# esp_4g_gp10-a.net
KiCad netlist of a schematic drawn in EasyEDA Pro
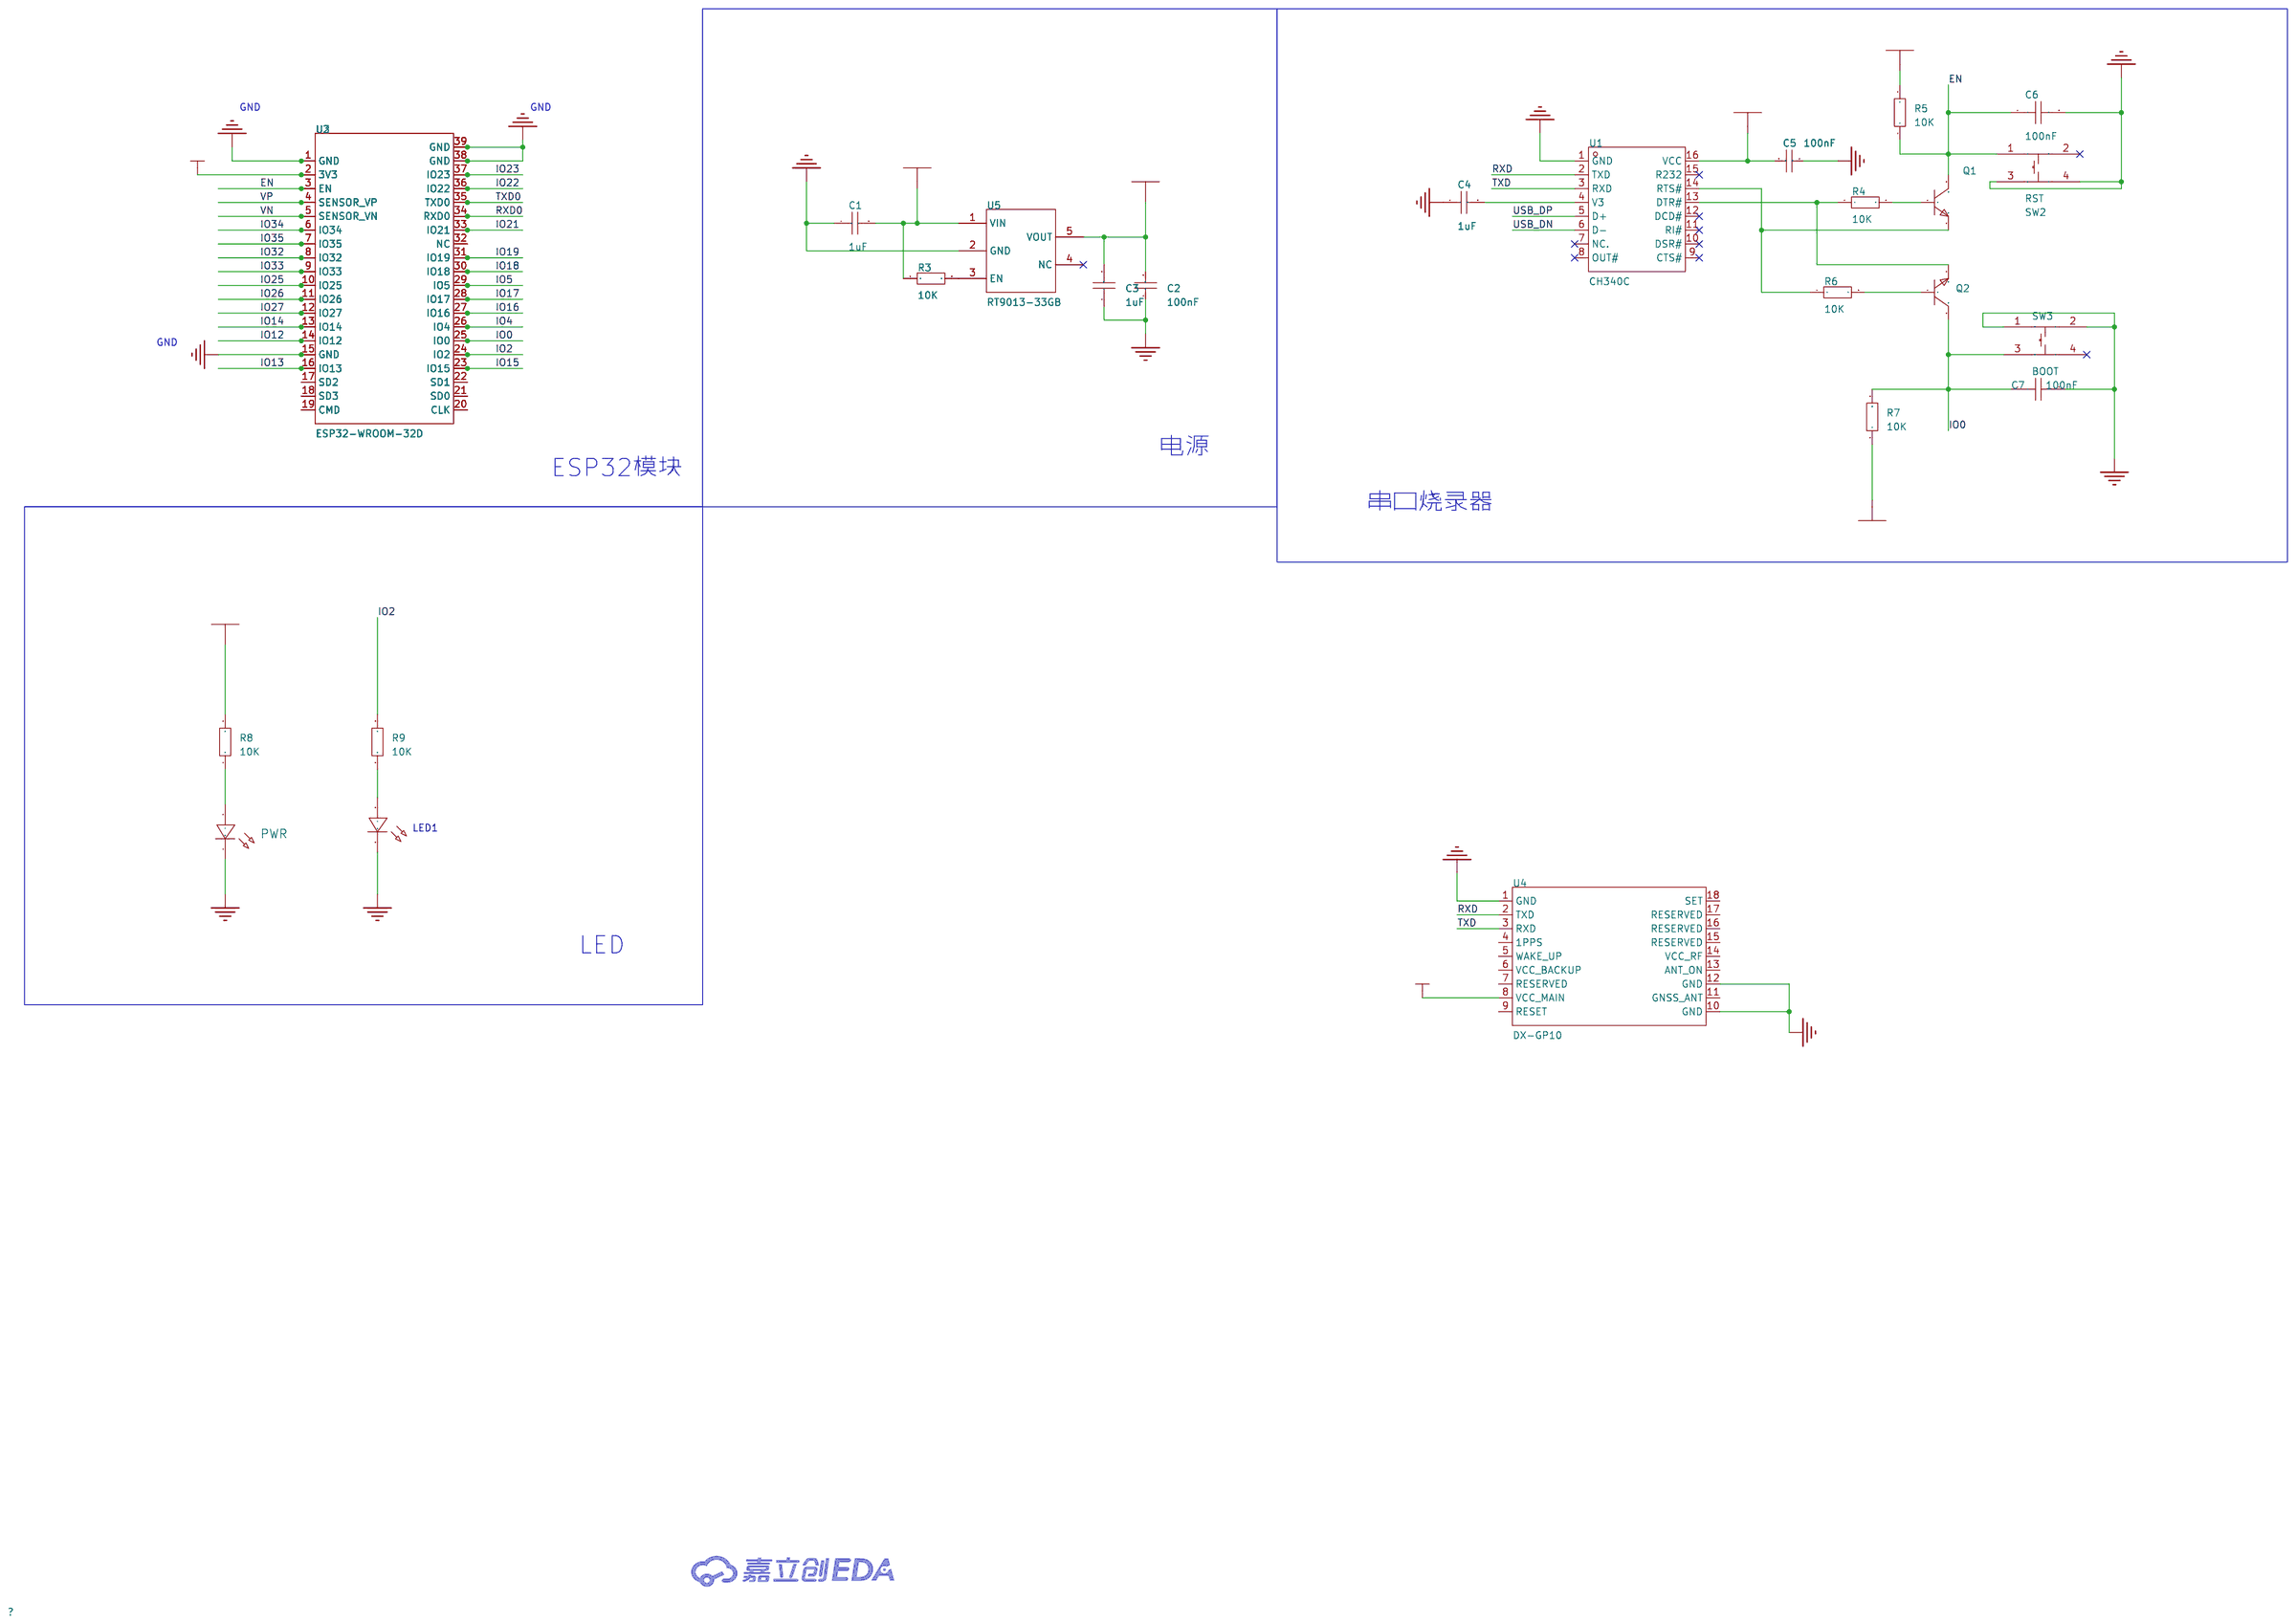
[diagram p0: schematic sheet]

(export (version "E")
  (design (tool "Eeschema 10.0.6"))
  (components
    (comp (ref "C1")
      (value "1uF")
      (footprint "easyedapro:C0603")
      (description "容值:1uF;精度:±20%;额定电压:25V;材质(温度系数):Y5V;")
      (fields (field (name "Manufacturer Part") "0603F105M250NT") (field (name "Manufacturer") "FH(风华)"))
      (libsource (lib "easyedapro") (part "0603F105M250NT"))
    )
    (comp (ref "C2")
      (value "100nF")
      (footprint "easyedapro:C0402")
      (description "温度系数:X7R;容值:100nF;精度:±5%;额定电压:16V;")
      (fields (field (name "Manufacturer Part") "0402B104J160NT") (field (name "Manufacturer") "FH(风华)"))
      (libsource (lib "easyedapro") (part "0402B104J160NT"))
    )
    (comp (ref "C3")
      (value "1uF")
      (footprint "easyedapro:C0603")
      (description "容值:1uF;精度:±20%;额定电压:25V;材质(温度系数):Y5V;")
      (fields (field (name "Manufacturer Part") "0603F105M250NT") (field (name "Manufacturer") "FH(风华)"))
      (libsource (lib "easyedapro") (part "0603F105M250NT"))
    )
    (comp (ref "C4")
      (value "1uF")
      (footprint "easyedapro:C0603")
      (description "容值:1uF;精度:±20%;额定电压:25V;材质(温度系数):Y5V;")
      (fields (field (name "Manufacturer Part") "0603F105M250NT") (field (name "Manufacturer") "FH(风华)"))
      (libsource (lib "easyedapro") (part "0603F105M250NT"))
    )
    (comp (ref "C5")
      (value "100nF")
      (footprint "easyedapro:C0402")
      (description "温度系数:X7R;容值:100nF;精度:±5%;额定电压:16V;")
      (fields (field (name "Manufacturer Part") "0402B104J160NT") (field (name "Manufacturer") "FH(风华)"))
      (libsource (lib "easyedapro") (part "0402B104J160NT"))
    )
    (comp (ref "C6")
      (value "100nF")
      (footprint "easyedapro:C0603")
      (libsource (lib "easyedapro") (part "CapAcitance"))
    )
    (comp (ref "C7")
      (value "100nF")
      (footprint "easyedapro:C0603")
      (libsource (lib "easyedapro") (part "CapAcitance"))
    )
    (comp (ref "LED1")
      (value "~")
      (footprint "easyedapro:LED_0603")
      (libsource (lib "easyedapro") (part "LED_G"))
    )
    (comp (ref "PWR")
      (value "~")
      (footprint "easyedapro:LED_0603")
      (libsource (lib "easyedapro") (part "LED_R"))
    )
    (comp (ref "Q1")
      (value "~")
      (footprint "easyedapro:S8050_SOT-23")
      (libsource (lib "easyedapro") (part "NPN"))
    )
    (comp (ref "Q2")
      (value "~")
      (footprint "easyedapro:S8050_SOT-23")
      (libsource (lib "easyedapro") (part "NPN"))
    )
    (comp (ref "R3") (value "10K") (footprint "easyedapro:R0603") (libsource (lib "easyedapro") (part "电阻")))
    (comp (ref "R4") (value "10K") (footprint "easyedapro:R0603") (libsource (lib "easyedapro") (part "电阻")))
    (comp (ref "R5") (value "10K") (footprint "easyedapro:R0603") (libsource (lib "easyedapro") (part "电阻")))
    (comp (ref "R6") (value "10K") (footprint "easyedapro:R0603") (libsource (lib "easyedapro") (part "电阻")))
    (comp (ref "R7") (value "10K") (footprint "easyedapro:R0603") (libsource (lib "easyedapro") (part "电阻")))
    (comp (ref "R8") (value "10K") (footprint "easyedapro:R0603") (libsource (lib "easyedapro") (part "电阻")))
    (comp (ref "R9") (value "10K") (footprint "easyedapro:R0603") (libsource (lib "easyedapro") (part "电阻")))
    (comp (ref "SW2")
      (value "RST")
      (footprint "easyedapro:KEY-SMD_4P-L4.2-W3.2-P2.20-LS4.6")
      (description "触点电流:50mA;额定电压(DC):16V;电路结构:单刀单掷;安装方式:立贴;按钮形状:椭圆形按钮;带灯:-;开关长度:4.2mm;开关宽度:3.2mm;开关高度:2.5mm;")
      (fields (field (name "Manufacturer") "ALPSALPINE(阿尔卑斯阿尔派)"))
      (libsource (lib "easyedapro") (part "SKRPACE010"))
    )
    (comp (ref "SW3")
      (value "BOOT")
      (footprint "easyedapro:KEY-SMD_4P-L4.2-W3.2-P2.20-LS4.6")
      (description "触点电流:50mA;额定电压(DC):16V;电路结构:单刀单掷;安装方式:立贴;按钮形状:椭圆形按钮;带灯:-;开关长度:4.2mm;开关宽度:3.2mm;开关高度:2.5mm;")
      (fields (field (name "Manufacturer") "ALPSALPINE(阿尔卑斯阿尔派)"))
      (libsource (lib "easyedapro") (part "SKRPACE010"))
    )
    (comp (ref "U1")
      (value "CH340C")
      (footprint "easyedapro:SOP-16_L10.0-W3.9-P1.27-LS6.0-BL")
      (description "应用功能:收发器;接口协议:USB 2.0;数据速率:2Mbps;")
      (fields (field (name "Manufacturer") "WCH(南京沁恒)"))
      (libsource (lib "easyedapro") (part "CH340C"))
    )
    (comp (ref "U2")
      (value "ESP32-WROOM-32D")
      (footprint "easyedapro:WIFIM-SMD_ESP32-WROOM-32D")
      (libsource (lib "easyedapro") (part "ESP32-WROOM-32D_C503588"))
    )
    (comp (ref "U3")
      (value "ESP32-WROOM-32D")
      (footprint "easyedapro:WIFIM-SMD_ESP32-WROOM-32D")
      (libsource (lib "easyedapro") (part "ESP32-WROOM-32D_C503588"))
    )
    (comp (ref "U4")
      (value "DX-GP10")
      (footprint "easyedapro:COMM-SMD_18P-L10.1-W9.7-P1.1-TL_L76-LB")
      (libsource (lib "easyedapro") (part "DX-GP10"))
    )
    (comp (ref "U5")
      (value "RT9013-33GB")
      (footprint "easyedapro:SOT-23-5_L3.0-W1.7-P0.95-LS2.8-BL")
      (description "输出类型:固定;最大输入电压:5.5V;输出电压:3.3V;输出电流:500mA;电源纹波抑制比(PSRR):50dB@(10kHz);输出极性:正极;")
      (fields (field (name "Manufacturer") "RICHTEK(立锜)"))
      (libsource (lib "easyedapro") (part "RT9013-33GB"))
    )
  )
  (nets
    (net (code "1") (name "/EN") (class "Default")
      (node (ref "C6") (pin "1") (pinfunction "1_1") (pintype "input"))
      (node (ref "Q1") (pin "3") (pinfunction "3_3") (pintype "unspecified"))
      (node (ref "R5") (pin "1") (pinfunction "1_1") (pintype "input"))
      (node (ref "SW2") (pin "1") (pinfunction "1_1") (pintype "input"))
      (node (ref "U2") (pin "3") (pinfunction "EN_3") (pintype "unspecified"))
      (node (ref "U3") (pin "3") (pinfunction "EN_3") (pintype "unspecified"))
    )
    (net (code "2") (name "/IO0") (class "Default")
      (node (ref "C7") (pin "1") (pinfunction "1_1") (pintype "input"))
      (node (ref "Q2") (pin "3") (pinfunction "3_3") (pintype "unspecified"))
      (node (ref "R7") (pin "2") (pinfunction "2_2") (pintype "input"))
      (node (ref "SW3") (pin "3") (pinfunction "3_3") (pintype "input"))
      (node (ref "U2") (pin "25") (pinfunction "IO0_25") (pintype "unspecified"))
      (node (ref "U3") (pin "25") (pinfunction "IO0_25") (pintype "unspecified"))
    )
    (net (code "3") (name "/IO2") (class "Default")
      (node (ref "R9") (pin "2") (pinfunction "2_2") (pintype "input"))
      (node (ref "U2") (pin "24") (pinfunction "IO2_24") (pintype "unspecified"))
      (node (ref "U3") (pin "24") (pinfunction "IO2_24") (pintype "unspecified"))
    )
    (net (code "4") (name "/IO4") (class "Default")
      (node (ref "U2") (pin "26") (pinfunction "IO4_26") (pintype "unspecified"))
      (node (ref "U3") (pin "26") (pinfunction "IO4_26") (pintype "unspecified"))
    )
    (net (code "5") (name "/IO5") (class "Default")
      (node (ref "U2") (pin "29") (pinfunction "IO5_29") (pintype "unspecified"))
      (node (ref "U3") (pin "29") (pinfunction "IO5_29") (pintype "unspecified"))
    )
    (net (code "6") (name "/IO12") (class "Default")
      (node (ref "U2") (pin "14") (pinfunction "IO12_14") (pintype "unspecified"))
      (node (ref "U3") (pin "14") (pinfunction "IO12_14") (pintype "unspecified"))
    )
    (net (code "7") (name "/IO13") (class "Default")
      (node (ref "U2") (pin "16") (pinfunction "IO13_16") (pintype "unspecified"))
      (node (ref "U3") (pin "16") (pinfunction "IO13_16") (pintype "unspecified"))
    )
    (net (code "8") (name "/IO14") (class "Default")
      (node (ref "U2") (pin "13") (pinfunction "IO14_13") (pintype "unspecified"))
      (node (ref "U3") (pin "13") (pinfunction "IO14_13") (pintype "unspecified"))
    )
    (net (code "9") (name "/IO15") (class "Default")
      (node (ref "U2") (pin "23") (pinfunction "IO15_23") (pintype "unspecified"))
      (node (ref "U3") (pin "23") (pinfunction "IO15_23") (pintype "unspecified"))
    )
    (net (code "10") (name "/IO16") (class "Default")
      (node (ref "U2") (pin "27") (pinfunction "IO16_27") (pintype "unspecified"))
      (node (ref "U3") (pin "27") (pinfunction "IO16_27") (pintype "unspecified"))
    )
    (net (code "11") (name "/IO17") (class "Default")
      (node (ref "U2") (pin "28") (pinfunction "IO17_28") (pintype "unspecified"))
      (node (ref "U3") (pin "28") (pinfunction "IO17_28") (pintype "unspecified"))
    )
    (net (code "12") (name "/IO18") (class "Default")
      (node (ref "U2") (pin "30") (pinfunction "IO18_30") (pintype "unspecified"))
      (node (ref "U3") (pin "30") (pinfunction "IO18_30") (pintype "unspecified"))
    )
    (net (code "13") (name "/IO19") (class "Default")
      (node (ref "U2") (pin "31") (pinfunction "IO19_31") (pintype "unspecified"))
      (node (ref "U3") (pin "31") (pinfunction "IO19_31") (pintype "unspecified"))
    )
    (net (code "14") (name "/IO21") (class "Default")
      (node (ref "U2") (pin "33") (pinfunction "IO21_33") (pintype "unspecified"))
      (node (ref "U3") (pin "33") (pinfunction "IO21_33") (pintype "unspecified"))
    )
    (net (code "15") (name "/IO22") (class "Default")
      (node (ref "U2") (pin "36") (pinfunction "IO22_36") (pintype "unspecified"))
      (node (ref "U3") (pin "36") (pinfunction "IO22_36") (pintype "unspecified"))
    )
    (net (code "16") (name "/IO23") (class "Default")
      (node (ref "U2") (pin "37") (pinfunction "IO23_37") (pintype "unspecified"))
      (node (ref "U3") (pin "37") (pinfunction "IO23_37") (pintype "unspecified"))
    )
    (net (code "17") (name "/IO25") (class "Default")
      (node (ref "U2") (pin "10") (pinfunction "IO25_10") (pintype "unspecified"))
      (node (ref "U3") (pin "10") (pinfunction "IO25_10") (pintype "unspecified"))
    )
    (net (code "18") (name "/IO26") (class "Default")
      (node (ref "U2") (pin "11") (pinfunction "IO26_11") (pintype "unspecified"))
      (node (ref "U3") (pin "11") (pinfunction "IO26_11") (pintype "unspecified"))
    )
    (net (code "19") (name "/IO27") (class "Default")
      (node (ref "U2") (pin "12") (pinfunction "IO27_12") (pintype "unspecified"))
      (node (ref "U3") (pin "12") (pinfunction "IO27_12") (pintype "unspecified"))
    )
    (net (code "20") (name "/IO32") (class "Default")
      (node (ref "U2") (pin "8") (pinfunction "IO32_8") (pintype "unspecified"))
      (node (ref "U3") (pin "8") (pinfunction "IO32_8") (pintype "unspecified"))
    )
    (net (code "21") (name "/IO33") (class "Default")
      (node (ref "U2") (pin "9") (pinfunction "IO33_9") (pintype "unspecified"))
      (node (ref "U3") (pin "9") (pinfunction "IO33_9") (pintype "unspecified"))
    )
    (net (code "22") (name "/IO34") (class "Default")
      (node (ref "U2") (pin "6") (pinfunction "IO34_6") (pintype "unspecified"))
      (node (ref "U3") (pin "6") (pinfunction "IO34_6") (pintype "unspecified"))
    )
    (net (code "23") (name "/IO35") (class "Default")
      (node (ref "U2") (pin "7") (pinfunction "IO35_7") (pintype "unspecified"))
      (node (ref "U3") (pin "7") (pinfunction "IO35_7") (pintype "unspecified"))
    )
    (net (code "24") (name "/RXD") (class "Default")
      (node (ref "U1") (pin "2") (pinfunction "TXD_2") (pintype "unspecified"))
      (node (ref "U4") (pin "2") (pinfunction "TXD_2") (pintype "unspecified"))
    )
    (net (code "25") (name "/RXD0") (class "Default")
      (node (ref "U2") (pin "34") (pinfunction "RXD0_34") (pintype "unspecified"))
      (node (ref "U3") (pin "34") (pinfunction "RXD0_34") (pintype "unspecified"))
    )
    (net (code "26") (name "/TXD") (class "Default")
      (node (ref "U1") (pin "3") (pinfunction "RXD_3") (pintype "unspecified"))
      (node (ref "U4") (pin "3") (pinfunction "RXD_3") (pintype "unspecified"))
    )
    (net (code "27") (name "/TXD0") (class "Default")
      (node (ref "U2") (pin "35") (pinfunction "TXD0_35") (pintype "unspecified"))
      (node (ref "U3") (pin "35") (pinfunction "TXD0_35") (pintype "unspecified"))
    )
    (net (code "28") (name "/USB_DN") (class "Default")
      (node (ref "U1") (pin "6") (pinfunction "D-_6") (pintype "unspecified"))
    )
    (net (code "29") (name "/USB_DP") (class "Default")
      (node (ref "U1") (pin "5") (pinfunction "D+_5") (pintype "unspecified"))
    )
    (net (code "30") (name "/VN") (class "Default")
      (node (ref "U2") (pin "5") (pinfunction "SENSOR_VN_5") (pintype "unspecified"))
      (node (ref "U3") (pin "5") (pinfunction "SENSOR_VN_5") (pintype "unspecified"))
    )
    (net (code "31") (name "/VP") (class "Default")
      (node (ref "U2") (pin "4") (pinfunction "SENSOR_VP_4") (pintype "unspecified"))
      (node (ref "U3") (pin "4") (pinfunction "SENSOR_VP_4") (pintype "unspecified"))
    )
    (net (code "32") (name "3.3V") (class "Default")
      (node (ref "U2") (pin "2") (pinfunction "3V3_2") (pintype "unspecified"))
      (node (ref "U3") (pin "2") (pinfunction "3V3_2") (pintype "unspecified"))
    )
    (net (code "33") (name "3V3") (class "Default")
      (node (ref "C2") (pin "2") (pinfunction "2_2") (pintype "input"))
      (node (ref "C3") (pin "2") (pinfunction "2_2") (pintype "input"))
      (node (ref "R5") (pin "2") (pinfunction "2_2") (pintype "input"))
      (node (ref "R7") (pin "1") (pinfunction "1_1") (pintype "input"))
      (node (ref "R8") (pin "2") (pinfunction "2_2") (pintype "input"))
      (node (ref "U5") (pin "5") (pinfunction "VOUT_5") (pintype "unspecified"))
    )
    (net (code "34") (name "GND") (class "Default")
      (node (ref "C1") (pin "1") (pinfunction "1_1") (pintype "input"))
      (node (ref "C2") (pin "1") (pinfunction "1_1") (pintype "input"))
      (node (ref "C3") (pin "1") (pinfunction "1_1") (pintype "input"))
      (node (ref "C4") (pin "1") (pinfunction "1_1") (pintype "input"))
      (node (ref "C5") (pin "1") (pinfunction "1_1") (pintype "input"))
      (node (ref "C6") (pin "2") (pinfunction "2_2") (pintype "input"))
      (node (ref "C7") (pin "2") (pinfunction "2_2") (pintype "input"))
      (node (ref "LED1") (pin "1") (pinfunction "C_1") (pintype "input"))
      (node (ref "PWR") (pin "1") (pinfunction "C_1") (pintype "input"))
      (node (ref "SW2") (pin "3") (pinfunction "3_3") (pintype "input"))
      (node (ref "SW2") (pin "4") (pinfunction "4_4") (pintype "input"))
      (node (ref "SW3") (pin "1") (pinfunction "1_1") (pintype "input"))
      (node (ref "SW3") (pin "2") (pinfunction "2_2") (pintype "input"))
      (node (ref "U1") (pin "1") (pinfunction "GND_1") (pintype "unspecified"))
      (node (ref "U2") (pin "1") (pinfunction "GND_1") (pintype "unspecified"))
      (node (ref "U2") (pin "15") (pinfunction "GND_15") (pintype "unspecified"))
      (node (ref "U2") (pin "38") (pinfunction "GND_38") (pintype "unspecified"))
      (node (ref "U2") (pin "39") (pinfunction "GND_39") (pintype "unspecified"))
      (node (ref "U3") (pin "1") (pinfunction "GND_1") (pintype "unspecified"))
      (node (ref "U3") (pin "15") (pinfunction "GND_15") (pintype "unspecified"))
      (node (ref "U3") (pin "38") (pinfunction "GND_38") (pintype "unspecified"))
      (node (ref "U3") (pin "39") (pinfunction "GND_39") (pintype "unspecified"))
      (node (ref "U4") (pin "1") (pinfunction "GND_1") (pintype "unspecified"))
      (node (ref "U4") (pin "10") (pinfunction "GND_10") (pintype "unspecified"))
      (node (ref "U4") (pin "12") (pinfunction "GND_12") (pintype "unspecified"))
      (node (ref "U5") (pin "2") (pinfunction "GND_2") (pintype "unspecified"))
    )
    (net (code "35") (name "Net-(LED1-A)") (class "Default")
      (node (ref "LED1") (pin "2") (pinfunction "A_2") (pintype "input"))
      (node (ref "R9") (pin "1") (pinfunction "1_1") (pintype "input"))
    )
    (net (code "36") (name "Net-(PWR-A)") (class "Default")
      (node (ref "PWR") (pin "2") (pinfunction "A_2") (pintype "input"))
      (node (ref "R8") (pin "1") (pinfunction "1_1") (pintype "input"))
    )
    (net (code "37") (name "Net-(Q1-Pad1)") (class "Default")
      (node (ref "Q1") (pin "1") (pinfunction "1_1") (pintype "unspecified"))
      (node (ref "R4") (pin "2") (pinfunction "2_2") (pintype "input"))
    )
    (net (code "38") (name "Net-(Q2-Pad1)") (class "Default")
      (node (ref "Q2") (pin "1") (pinfunction "1_1") (pintype "unspecified"))
      (node (ref "R6") (pin "2") (pinfunction "2_2") (pintype "input"))
    )
    (net (code "39") (name "Net-(U1-DTR#)") (class "Default")
      (node (ref "Q2") (pin "2") (pinfunction "2_2") (pintype "unspecified"))
      (node (ref "R4") (pin "1") (pinfunction "1_1") (pintype "input"))
      (node (ref "U1") (pin "13") (pinfunction "DTR#_13") (pintype "unspecified"))
    )
    (net (code "40") (name "Net-(U1-RTS#)") (class "Default")
      (node (ref "Q1") (pin "2") (pinfunction "2_2") (pintype "unspecified"))
      (node (ref "R6") (pin "1") (pinfunction "1_1") (pintype "input"))
      (node (ref "U1") (pin "14") (pinfunction "RTS#_14") (pintype "unspecified"))
    )
    (net (code "41") (name "Net-(U1-V3)") (class "Default")
      (node (ref "C4") (pin "2") (pinfunction "2_2") (pintype "input"))
      (node (ref "U1") (pin "4") (pinfunction "V3_4") (pintype "unspecified"))
    )
    (net (code "42") (name "Net-(U2-CLK)") (class "Default")
      (node (ref "U2") (pin "20") (pinfunction "CLK_20") (pintype "unspecified"))
      (node (ref "U3") (pin "20") (pinfunction "CLK_20") (pintype "unspecified"))
    )
    (net (code "43") (name "Net-(U2-CMD)") (class "Default")
      (node (ref "U2") (pin "19") (pinfunction "CMD_19") (pintype "unspecified"))
      (node (ref "U3") (pin "19") (pinfunction "CMD_19") (pintype "unspecified"))
    )
    (net (code "44") (name "Net-(U2-NC)") (class "Default")
      (node (ref "U2") (pin "32") (pinfunction "NC_32") (pintype "unspecified"))
      (node (ref "U3") (pin "32") (pinfunction "NC_32") (pintype "unspecified"))
    )
    (net (code "45") (name "Net-(U2-SD0)") (class "Default")
      (node (ref "U2") (pin "21") (pinfunction "SD0_21") (pintype "unspecified"))
      (node (ref "U3") (pin "21") (pinfunction "SD0_21") (pintype "unspecified"))
    )
    (net (code "46") (name "Net-(U2-SD1)") (class "Default")
      (node (ref "U2") (pin "22") (pinfunction "SD1_22") (pintype "unspecified"))
      (node (ref "U3") (pin "22") (pinfunction "SD1_22") (pintype "unspecified"))
    )
    (net (code "47") (name "Net-(U2-SD2)") (class "Default")
      (node (ref "U2") (pin "17") (pinfunction "SD2_17") (pintype "unspecified"))
      (node (ref "U3") (pin "17") (pinfunction "SD2_17") (pintype "unspecified"))
    )
    (net (code "48") (name "Net-(U2-SD3)") (class "Default")
      (node (ref "U2") (pin "18") (pinfunction "SD3_18") (pintype "unspecified"))
      (node (ref "U3") (pin "18") (pinfunction "SD3_18") (pintype "unspecified"))
    )
    (net (code "49") (name "Net-(U5-EN)") (class "Default")
      (node (ref "R3") (pin "2") (pinfunction "2_2") (pintype "input"))
      (node (ref "U5") (pin "3") (pinfunction "EN_3") (pintype "unspecified"))
    )
    (net (code "50") (name "VBUS") (class "Default")
      (node (ref "C1") (pin "2") (pinfunction "2_2") (pintype "input"))
      (node (ref "C5") (pin "2") (pinfunction "2_2") (pintype "input"))
      (node (ref "R3") (pin "1") (pinfunction "1_1") (pintype "input"))
      (node (ref "U1") (pin "16") (pinfunction "VCC_16") (pintype "unspecified"))
      (node (ref "U5") (pin "1") (pinfunction "VIN_1") (pintype "unspecified"))
    )
    (net (code "51") (name "VCC3.3V") (class "Default")
      (node (ref "U4") (pin "8") (pinfunction "VCC_MAIN_8") (pintype "unspecified"))
    )
    (net (code "52") (name "unconnected-(SW2-Pad2)") (class "Default")
      (node (ref "SW2") (pin "2") (pinfunction "2_2") (pintype "input+no_connect"))
    )
    (net (code "53") (name "unconnected-(SW3-Pad4)") (class "Default")
      (node (ref "SW3") (pin "4") (pinfunction "4_4") (pintype "input+no_connect"))
    )
    (net (code "54") (name "unconnected-(U1-CTS#-Pad9)") (class "Default")
      (node (ref "U1") (pin "9") (pinfunction "CTS#_9") (pintype "unspecified+no_connect"))
    )
    (net (code "55") (name "unconnected-(U1-DCD#-Pad12)") (class "Default")
      (node (ref "U1") (pin "12") (pinfunction "DCD#_12") (pintype "unspecified+no_connect"))
    )
    (net (code "56") (name "unconnected-(U1-DSR#-Pad10)") (class "Default")
      (node (ref "U1") (pin "10") (pinfunction "DSR#_10") (pintype "unspecified+no_connect"))
    )
    (net (code "57") (name "unconnected-(U1-NC.-Pad7)") (class "Default")
      (node (ref "U1") (pin "7") (pinfunction "NC._7") (pintype "unspecified+no_connect"))
    )
    (net (code "58") (name "unconnected-(U1-OUT#-Pad8)") (class "Default")
      (node (ref "U1") (pin "8") (pinfunction "OUT#_8") (pintype "unspecified+no_connect"))
    )
    (net (code "59") (name "unconnected-(U1-R232-Pad15)") (class "Default")
      (node (ref "U1") (pin "15") (pinfunction "R232_15") (pintype "unspecified+no_connect"))
    )
    (net (code "60") (name "unconnected-(U1-RI#-Pad11)") (class "Default")
      (node (ref "U1") (pin "11") (pinfunction "RI#_11") (pintype "unspecified+no_connect"))
    )
    (net (code "61") (name "unconnected-(U4-1PPS-Pad4)") (class "Default")
      (node (ref "U4") (pin "4") (pinfunction "1PPS_4") (pintype "unspecified"))
    )
    (net (code "62") (name "unconnected-(U4-ANT_ON-Pad13)") (class "Default")
      (node (ref "U4") (pin "13") (pinfunction "ANT_ON_13") (pintype "unspecified"))
    )
    (net (code "63") (name "unconnected-(U4-GNSS_ANT-Pad11)") (class "Default")
      (node (ref "U4") (pin "11") (pinfunction "GNSS_ANT_11") (pintype "unspecified"))
    )
    (net (code "64") (name "unconnected-(U4-RESERVED-Pad7)") (class "Default")
      (node (ref "U4") (pin "7") (pinfunction "RESERVED_7") (pintype "unspecified"))
    )
    (net (code "65") (name "unconnected-(U4-RESERVED-Pad15)") (class "Default")
      (node (ref "U4") (pin "15") (pinfunction "RESERVED_15") (pintype "unspecified"))
    )
    (net (code "66") (name "unconnected-(U4-RESERVED-Pad16)") (class "Default")
      (node (ref "U4") (pin "16") (pinfunction "RESERVED_16") (pintype "unspecified"))
    )
    (net (code "67") (name "unconnected-(U4-RESERVED-Pad17)") (class "Default")
      (node (ref "U4") (pin "17") (pinfunction "RESERVED_17") (pintype "unspecified"))
    )
    (net (code "68") (name "unconnected-(U4-RESET-Pad9)") (class "Default")
      (node (ref "U4") (pin "9") (pinfunction "RESET_9") (pintype "unspecified"))
    )
    (net (code "69") (name "unconnected-(U4-SET-Pad18)") (class "Default")
      (node (ref "U4") (pin "18") (pinfunction "SET_18") (pintype "unspecified"))
    )
    (net (code "70") (name "unconnected-(U4-VCC_BACKUP-Pad6)") (class "Default")
      (node (ref "U4") (pin "6") (pinfunction "VCC_BACKUP_6") (pintype "unspecified"))
    )
    (net (code "71") (name "unconnected-(U4-VCC_RF-Pad14)") (class "Default")
      (node (ref "U4") (pin "14") (pinfunction "VCC_RF_14") (pintype "unspecified"))
    )
    (net (code "72") (name "unconnected-(U4-WAKE_UP-Pad5)") (class "Default")
      (node (ref "U4") (pin "5") (pinfunction "WAKE_UP_5") (pintype "unspecified"))
    )
    (net (code "73") (name "unconnected-(U5-NC-Pad4)") (class "Default")
      (node (ref "U5") (pin "4") (pinfunction "NC_4") (pintype "unspecified+no_connect"))
    )
  )
)
